# Converter_12V-0V9.net
KiCad netlist of a schematic drawn in Altium Designer
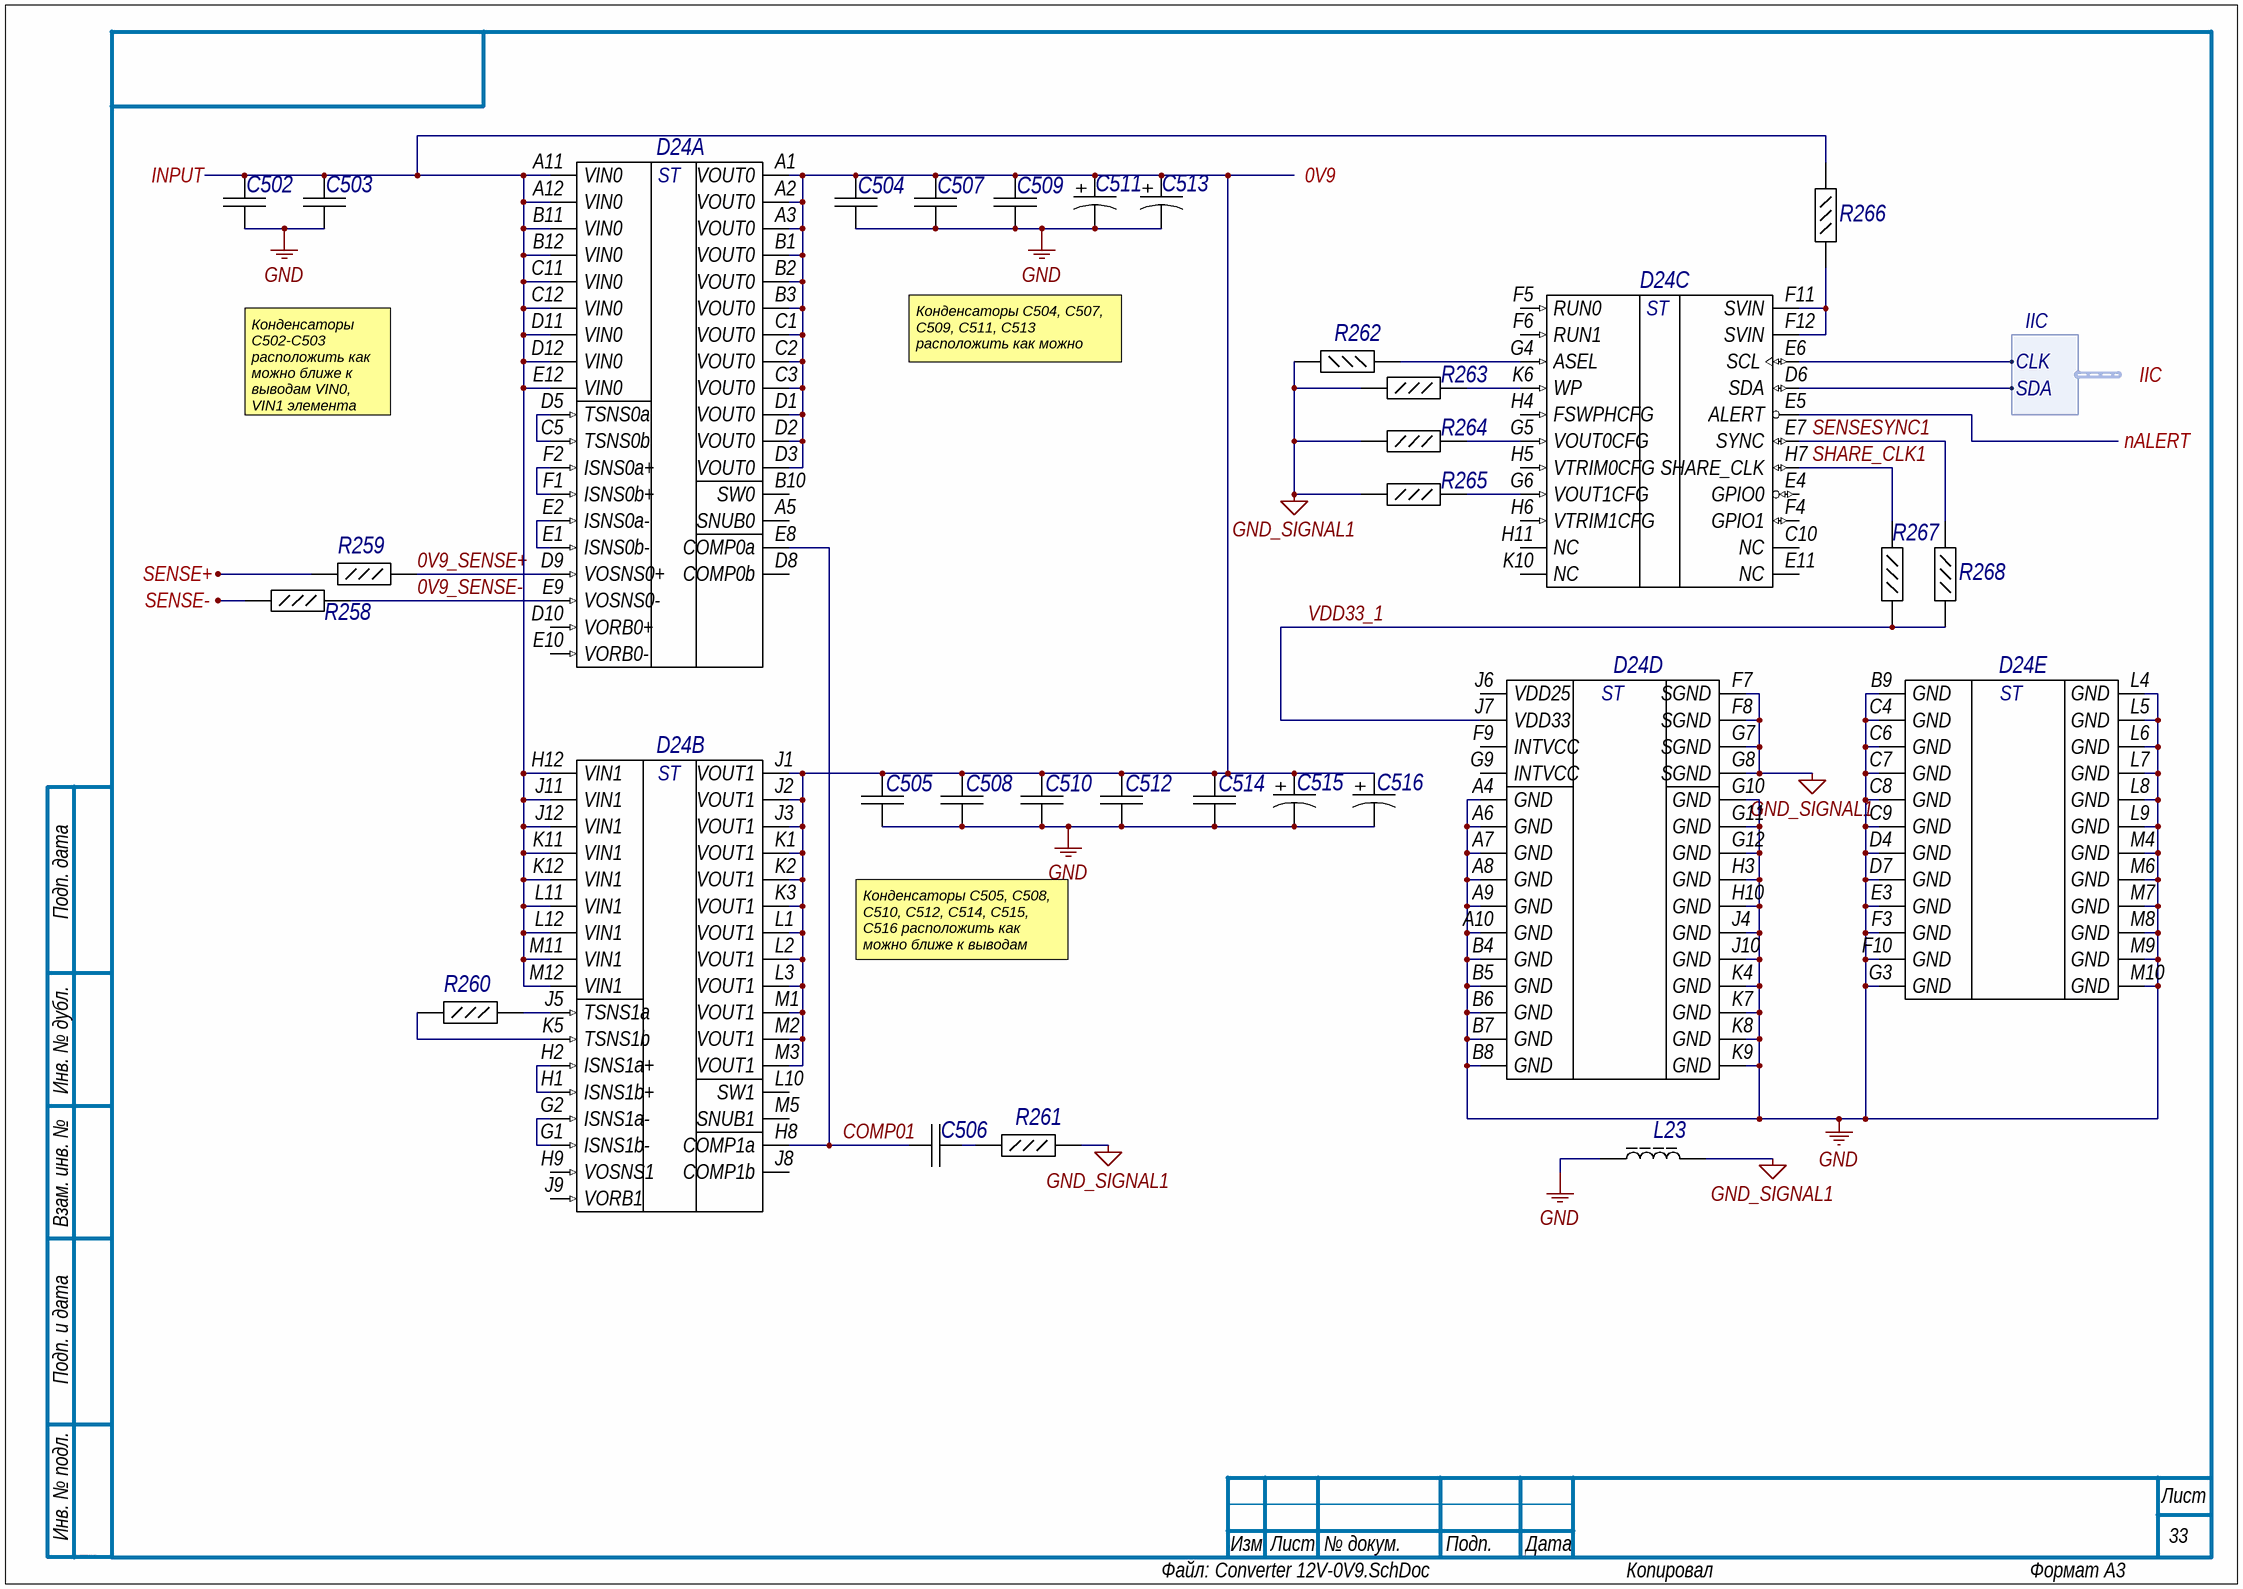
[diagram p0: Converter 12V-0V9.SchDoc]

(export (version "E")
  (design (tool "Eeschema 10.0.6"))
  (components
    (comp (ref "C502")
      (value "GRM31CR61E226KE15L")
      (footprint "CAPC3216X180X55ML20T25")
      (description "Chip Capacitor, 22 uF, +/- 10%, 25 V, -55 to 85 degC, 1206 (3216 Metric), RoHS, Tape and Reel")
      (fields (field (name "TOLERANCE") "10%"))
      (libsource (lib "MiniPC DB") (part "CAP_NP"))
    )
    (comp (ref "C503")
      (value "GRM31CR61E226KE15L")
      (footprint "CAPC3216X180X55ML20T25")
      (description "Chip Capacitor, 22 uF, +/- 10%, 25 V, -55 to 85 degC, 1206 (3216 Metric), RoHS, Tape and Reel")
      (fields (field (name "TOLERANCE") "10%"))
      (libsource (lib "MiniPC DB") (part "CAP_NP"))
    )
    (comp (ref "C504")
      (value "GRM31CR60J107ME39L")
      (footprint "CAPC3216X190X55ML30T25")
      (description "Chip Capacitor, 100 uF, +/- 20%, 6.3 V, -55 to 85 degC, 1206 (3216 Metric), RoHS, Tape and Reel")
      (fields (field (name "TOLERANCE") "20%"))
      (libsource (lib "MiniPC DB") (part "CAP_NP"))
    )
    (comp (ref "C505")
      (value "GRM31CR60J107ME39L")
      (footprint "CAPC3216X190X55ML30T25")
      (description "Chip Capacitor, 100 uF, +/- 20%, 6.3 V, -55 to 85 degC, 1206 (3216 Metric), RoHS, Tape and Reel")
      (fields (field (name "TOLERANCE") "20%"))
      (libsource (lib "MiniPC DB") (part "CAP_NP"))
    )
    (comp (ref "C506")
      (value "VJ0402Y182JXJCW1BC")
      (footprint "CAPC1005X55X23NL05T8")
      (description "Chip Capacitor, 1.8 nF, +/- 5%, 16 V, -55 to 125 degC, 0402 (1005 Metric), RoHS, Tape and Reel")
      (fields (field (name "TOLERANCE") "5%"))
      (libsource (lib "MiniPC DB") (part "CAP_NP"))
    )
    (comp (ref "C507")
      (value "GRM31CR60J107ME39L")
      (footprint "CAPC3216X190X55ML30T25")
      (description "Chip Capacitor, 100 uF, +/- 20%, 6.3 V, -55 to 85 degC, 1206 (3216 Metric), RoHS, Tape and Reel")
      (fields (field (name "TOLERANCE") "20%"))
      (libsource (lib "MiniPC DB") (part "CAP_NP"))
    )
    (comp (ref "C508")
      (value "GRM31CR60J107ME39L")
      (footprint "CAPC3216X190X55ML30T25")
      (description "Chip Capacitor, 100 uF, +/- 20%, 6.3 V, -55 to 85 degC, 1206 (3216 Metric), RoHS, Tape and Reel")
      (fields (field (name "TOLERANCE") "20%"))
      (libsource (lib "MiniPC DB") (part "CAP_NP"))
    )
    (comp (ref "C509")
      (value "GRM31CR60J107ME39L")
      (footprint "CAPC3216X190X55ML30T25")
      (description "Chip Capacitor, 100 uF, +/- 20%, 6.3 V, -55 to 85 degC, 1206 (3216 Metric), RoHS, Tape and Reel")
      (fields (field (name "TOLERANCE") "20%"))
      (libsource (lib "MiniPC DB") (part "CAP_NP"))
    )
    (comp (ref "C510")
      (value "GRM31CR60J107ME39L")
      (footprint "CAPC3216X190X55ML30T25")
      (description "Chip Capacitor, 100 uF, +/- 20%, 6.3 V, -55 to 85 degC, 1206 (3216 Metric), RoHS, Tape and Reel")
      (fields (field (name "TOLERANCE") "20%"))
      (libsource (lib "MiniPC DB") (part "CAP_NP"))
    )
    (comp (ref "C511")
      (value "6TPF330M9L")
      (footprint "PNSC-TPF-D3L_V")
      (description "Tantalum Capacitor, 330 uF, +/- 20%, 6.3 V, -55 to 105 degC, 2-Pin Molded, RoHS, Tape and Reel")
      (libsource (lib "MiniPC DB") (part "CAP_P"))
    )
    (comp (ref "C512")
      (value "GRM31CR60J107ME39L")
      (footprint "CAPC3216X190X55ML30T25")
      (description "Chip Capacitor, 100 uF, +/- 20%, 6.3 V, -55 to 85 degC, 1206 (3216 Metric), RoHS, Tape and Reel")
      (fields (field (name "TOLERANCE") "20%"))
      (libsource (lib "MiniPC DB") (part "CAP_NP"))
    )
    (comp (ref "C513")
      (value "6TPF330M9L")
      (footprint "PNSC-TPF-D3L_V")
      (description "Tantalum Capacitor, 330 uF, +/- 20%, 6.3 V, -55 to 105 degC, 2-Pin Molded, RoHS, Tape and Reel")
      (libsource (lib "MiniPC DB") (part "CAP_P"))
    )
    (comp (ref "C514")
      (value "GRM31CR60J107ME39L")
      (footprint "CAPC3216X190X55ML30T25")
      (description "Chip Capacitor, 100 uF, +/- 20%, 6.3 V, -55 to 85 degC, 1206 (3216 Metric), RoHS, Tape and Reel")
      (fields (field (name "TOLERANCE") "20%"))
      (libsource (lib "MiniPC DB") (part "CAP_NP"))
    )
    (comp (ref "C515")
      (value "6TPF330M9L")
      (footprint "PNSC-TPF-D3L_V")
      (description "Tantalum Capacitor, 330 uF, +/- 20%, 6.3 V, -55 to 105 degC, 2-Pin Molded, RoHS, Tape and Reel")
      (libsource (lib "MiniPC DB") (part "CAP_P"))
    )
    (comp (ref "C516")
      (value "6TPF330M9L")
      (footprint "PNSC-TPF-D3L_V")
      (description "Tantalum Capacitor, 330 uF, +/- 20%, 6.3 V, -55 to 105 degC, 2-Pin Molded, RoHS, Tape and Reel")
      (libsource (lib "MiniPC DB") (part "CAP_P"))
    )
    (comp (ref "D24")
      (value "LTM4677IY#PBF")
      (footprint "LT-BGA-144-05-08-1920_V")
      (fields (field (name "MANUFACTURER") "Linear Technology"))
      (libsource (lib "MiniPC DB") (part "LTM4677I"))
    )
    (comp (ref "L23")
      (value "742792609")
      (footprint "SMD-0603")
      (description "SMD EMI Suppression Ferrite Bead WE-CBF, Z = 30 Ohm")
      (libsource (lib "MiniPC DB") (part "Choke"))
    )
    (comp (ref "R258")
      (value "ERJ-2GE0R00X")
      (footprint "RESC1005X40X25LL05T05")
      (description "Chip Resistor, 0 mOhm, +/- 5%, 100 mW, -55 to 155 degC, 0402 (1005 Metric), RoHS, Tape and Reel")
      (fields (field (name "TOLERANCE") "5%") (field (name "MANUFACTURER") "Basic Passives"))
      (libsource (lib "MiniPC DB") (part "RES-0.05"))
    )
    (comp (ref "R259")
      (value "ERJ-2GE0R00X")
      (footprint "RESC1005X40X25LL05T05")
      (description "Chip Resistor, 0 mOhm, +/- 5%, 100 mW, -55 to 155 degC, 0402 (1005 Metric), RoHS, Tape and Reel")
      (fields (field (name "TOLERANCE") "5%") (field (name "MANUFACTURER") "Basic Passives"))
      (libsource (lib "MiniPC DB") (part "RES-0.05"))
    )
    (comp (ref "R260")
      (value "ERJ-2GE0R00X")
      (footprint "RESC1005X40X25LL05T05")
      (description "Chip Resistor, 0 mOhm, +/- 5%, 100 mW, -55 to 155 degC, 0402 (1005 Metric), RoHS, Tape and Reel")
      (fields (field (name "TOLERANCE") "5%") (field (name "MANUFACTURER") "Basic Passives"))
      (libsource (lib "MiniPC DB") (part "RES-0.05"))
    )
    (comp (ref "R261")
      (value "ERJ-2RKF1782X")
      (footprint "RESC1005X40X25LL05T05")
      (description "Chip Resistor, 17.8 KOhm, +/- 1%, 100 mW, -55 to 155 degC, 0402 (1005 Metric), RoHS, Tape and Reel")
      (fields (field (name "TOLERANCE") "1%") (field (name "MANUFACTURER") "Basic Passives"))
      (libsource (lib "MiniPC DB") (part "RES-0.05"))
    )
    (comp (ref "R262")
      (value "ERJ-2RKF1651X")
      (footprint "RESC1005X40X25LL05T05")
      (description "Chip Resistor, 1.65 KOhm, +/- 1%, 100 mW, -55 to 155 degC, 0402 (1005 Metric), RoHS, Tape and Reel")
      (fields (field (name "TOLERANCE") "1%") (field (name "MANUFACTURER") "Basic Passives"))
      (libsource (lib "") (part "RES-0.05_2"))
    )
    (comp (ref "R263")
      (value "ERJ-2RKF1002X")
      (footprint "RESC1005X40X25LL05T05")
      (description "Chip Resistor, 10 KOhm, +/- 1%, 100 mW, -55 to 155 degC, 0402 (1005 Metric), RoHS, Tape and Reel")
      (fields (field (name "TOLERANCE") "1%") (field (name "MANUFACTURER") "Basic Passives"))
      (libsource (lib "MiniPC DB") (part "RES-0.05"))
    )
    (comp (ref "R264")
      (value "ERJ-2RKF1651X")
      (footprint "RESC1005X40X25LL05T05")
      (description "Chip Resistor, 1.65 KOhm, +/- 1%, 100 mW, -55 to 155 degC, 0402 (1005 Metric), RoHS, Tape and Reel")
      (fields (field (name "TOLERANCE") "1%") (field (name "MANUFACTURER") "Basic Passives"))
      (libsource (lib "MiniPC DB") (part "RES-0.05"))
    )
    (comp (ref "R265")
      (value "ERJ-2RKF1651X")
      (footprint "RESC1005X40X25LL05T05")
      (description "Chip Resistor, 1.65 KOhm, +/- 1%, 100 mW, -55 to 155 degC, 0402 (1005 Metric), RoHS, Tape and Reel")
      (fields (field (name "TOLERANCE") "1%") (field (name "MANUFACTURER") "Basic Passives"))
      (libsource (lib "MiniPC DB") (part "RES-0.05"))
    )
    (comp (ref "R266")
      (value "ERJ-2GE0R00X")
      (footprint "RESC1005X40X25LL05T05")
      (description "Chip Resistor, 0 mOhm, +/- 5%, 100 mW, -55 to 155 degC, 0402 (1005 Metric), RoHS, Tape and Reel")
      (fields (field (name "TOLERANCE") "5%") (field (name "MANUFACTURER") "Basic Passives"))
      (libsource (lib "") (part "RES-0.05_1"))
    )
    (comp (ref "R267")
      (value "ERJ-2RKF1002X")
      (footprint "RESC1005X40X25LL05T05")
      (description "Chip Resistor, 10 KOhm, +/- 1%, 100 mW, -55 to 155 degC, 0402 (1005 Metric), RoHS, Tape and Reel")
      (fields (field (name "TOLERANCE") "1%") (field (name "MANUFACTURER") "Basic Passives"))
      (libsource (lib "") (part "RES-0.05_3"))
    )
    (comp (ref "R268")
      (value "ERJ-2RKF1002X")
      (footprint "RESC1005X40X25LL05T05")
      (description "Chip Resistor, 10 KOhm, +/- 1%, 100 mW, -55 to 155 degC, 0402 (1005 Metric), RoHS, Tape and Reel")
      (fields (field (name "TOLERANCE") "1%") (field (name "MANUFACTURER") "Basic Passives"))
      (libsource (lib "") (part "RES-0.05_3"))
    )
  )
  (nets
    (net (code "2") (name "/0V9") (class "Default")
      (node (ref "C504") (pin "2") (pinfunction "2_2") (pintype "passive"))
      (node (ref "C505") (pin "2") (pinfunction "2_2") (pintype "passive"))
      (node (ref "C507") (pin "2") (pinfunction "2_2") (pintype "passive"))
      (node (ref "C508") (pin "2") (pinfunction "2_2") (pintype "passive"))
      (node (ref "C509") (pin "2") (pinfunction "2_2") (pintype "passive"))
      (node (ref "C510") (pin "2") (pinfunction "2_2") (pintype "passive"))
      (node (ref "C511") (pin "1") (pinfunction "1_1") (pintype "passive"))
      (node (ref "C512") (pin "2") (pinfunction "2_2") (pintype "passive"))
      (node (ref "C513") (pin "1") (pinfunction "1_1") (pintype "passive"))
      (node (ref "C514") (pin "2") (pinfunction "2_2") (pintype "passive"))
      (node (ref "C515") (pin "1") (pinfunction "1_1") (pintype "passive"))
      (node (ref "C516") (pin "1") (pinfunction "1_1") (pintype "passive"))
      (node (ref "D24") (pin "A1") (pinfunction "VOUT0_A1") (pintype "power_in"))
      (node (ref "D24") (pin "A2") (pinfunction "VOUT0_A2") (pintype "power_in"))
      (node (ref "D24") (pin "A3") (pinfunction "VOUT0_A3") (pintype "power_in"))
      (node (ref "D24") (pin "B1") (pinfunction "VOUT0_B1") (pintype "power_in"))
      (node (ref "D24") (pin "B2") (pinfunction "VOUT0_B2") (pintype "power_in"))
      (node (ref "D24") (pin "B3") (pinfunction "VOUT0_B3") (pintype "power_in"))
      (node (ref "D24") (pin "C1") (pinfunction "VOUT0_C1") (pintype "power_in"))
      (node (ref "D24") (pin "C2") (pinfunction "VOUT0_C2") (pintype "power_in"))
      (node (ref "D24") (pin "C3") (pinfunction "VOUT0_C3") (pintype "power_in"))
      (node (ref "D24") (pin "D1") (pinfunction "VOUT0_D1") (pintype "power_in"))
      (node (ref "D24") (pin "D2") (pinfunction "VOUT0_D2") (pintype "power_in"))
      (node (ref "D24") (pin "D3") (pinfunction "VOUT0_D3") (pintype "power_in"))
      (node (ref "D24") (pin "J1") (pinfunction "VOUT1_J1") (pintype "power_in"))
      (node (ref "D24") (pin "J2") (pinfunction "VOUT1_J2") (pintype "power_in"))
      (node (ref "D24") (pin "J3") (pinfunction "VOUT1_J3") (pintype "power_in"))
      (node (ref "D24") (pin "K1") (pinfunction "VOUT1_K1") (pintype "power_in"))
      (node (ref "D24") (pin "K2") (pinfunction "VOUT1_K2") (pintype "power_in"))
      (node (ref "D24") (pin "K3") (pinfunction "VOUT1_K3") (pintype "power_in"))
      (node (ref "D24") (pin "L1") (pinfunction "VOUT1_L1") (pintype "power_in"))
      (node (ref "D24") (pin "L2") (pinfunction "VOUT1_L2") (pintype "power_in"))
      (node (ref "D24") (pin "L3") (pinfunction "VOUT1_L3") (pintype "power_in"))
      (node (ref "D24") (pin "M1") (pinfunction "VOUT1_M1") (pintype "power_in"))
      (node (ref "D24") (pin "M2") (pinfunction "VOUT1_M2") (pintype "power_in"))
      (node (ref "D24") (pin "M3") (pinfunction "VOUT1_M3") (pintype "power_in"))
    )
    (net (code "3") (name "/0V9_SENSE+") (class "Default")
      (node (ref "D24") (pin "D9") (pinfunction "VOSNS0+_D9") (pintype "input"))
      (node (ref "R259") (pin "1") (pinfunction "1_1") (pintype "passive"))
    )
    (net (code "4") (name "/0V9_SENSE-") (class "Default")
      (node (ref "D24") (pin "E9") (pinfunction "VOSNS0-_E9") (pintype "input"))
      (node (ref "R258") (pin "1") (pinfunction "1_1") (pintype "passive"))
    )
    (net (code "5") (name "/CLK") (class "Default")
      (node (ref "D24") (pin "E6") (pinfunction "SCL_E6") (pintype "bidirectional"))
    )
    (net (code "6") (name "/COMP01") (class "Default")
      (node (ref "C506") (pin "2") (pinfunction "2_2") (pintype "passive"))
      (node (ref "D24") (pin "E8") (pinfunction "COMP0a_E8") (pintype "passive"))
      (node (ref "D24") (pin "H8") (pinfunction "COMP1a_H8") (pintype "passive"))
    )
    (net (code "7") (name "/INPUT") (class "Default")
      (node (ref "C502") (pin "2") (pinfunction "2_2") (pintype "passive"))
      (node (ref "C503") (pin "2") (pinfunction "2_2") (pintype "passive"))
      (node (ref "D24") (pin "A11") (pinfunction "VIN0_A11") (pintype "power_in"))
      (node (ref "D24") (pin "A12") (pinfunction "VIN0_A12") (pintype "power_in"))
      (node (ref "D24") (pin "B11") (pinfunction "VIN0_B11") (pintype "power_in"))
      (node (ref "D24") (pin "B12") (pinfunction "VIN0_B12") (pintype "power_in"))
      (node (ref "D24") (pin "C11") (pinfunction "VIN0_C11") (pintype "power_in"))
      (node (ref "D24") (pin "C12") (pinfunction "VIN0_C12") (pintype "power_in"))
      (node (ref "D24") (pin "D11") (pinfunction "VIN0_D11") (pintype "power_in"))
      (node (ref "D24") (pin "D12") (pinfunction "VIN0_D12") (pintype "power_in"))
      (node (ref "D24") (pin "E12") (pinfunction "VIN0_E12") (pintype "power_in"))
      (node (ref "D24") (pin "H12") (pinfunction "VIN1_H12") (pintype "power_in"))
      (node (ref "D24") (pin "J11") (pinfunction "VIN1_J11") (pintype "power_in"))
      (node (ref "D24") (pin "J12") (pinfunction "VIN1_J12") (pintype "power_in"))
      (node (ref "D24") (pin "K11") (pinfunction "VIN1_K11") (pintype "power_in"))
      (node (ref "D24") (pin "K12") (pinfunction "VIN1_K12") (pintype "power_in"))
      (node (ref "D24") (pin "L11") (pinfunction "VIN1_L11") (pintype "power_in"))
      (node (ref "D24") (pin "L12") (pinfunction "VIN1_L12") (pintype "power_in"))
      (node (ref "D24") (pin "M11") (pinfunction "VIN1_M11") (pintype "power_in"))
      (node (ref "D24") (pin "M12") (pinfunction "VIN1_M12") (pintype "power_in"))
      (node (ref "R266") (pin "2") (pinfunction "2_2") (pintype "passive"))
    )
    (net (code "8") (name "/SDA") (class "Default")
      (node (ref "D24") (pin "D6") (pinfunction "SDA_D6") (pintype "bidirectional"))
    )
    (net (code "9") (name "/SENSE+") (class "Default")
      (node (ref "R259") (pin "2") (pinfunction "2_2") (pintype "passive"))
    )
    (net (code "10") (name "/SENSE-") (class "Default")
      (node (ref "R258") (pin "2") (pinfunction "2_2") (pintype "passive"))
    )
    (net (code "11") (name "/SENSESYNC1") (class "Default")
      (node (ref "D24") (pin "E7") (pinfunction "SYNC_E7") (pintype "bidirectional"))
      (node (ref "R268") (pin "1") (pinfunction "1_1") (pintype "passive"))
    )
    (net (code "12") (name "/SHARE_CLK1") (class "Default")
      (node (ref "D24") (pin "H7") (pinfunction "SHARE_CLK_H7") (pintype "bidirectional"))
      (node (ref "R267") (pin "1") (pinfunction "1_1") (pintype "passive"))
    )
    (net (code "13") (name "/VDD33_1") (class "Default")
      (node (ref "D24") (pin "J7") (pinfunction "VDD33_J7") (pintype "power_in"))
      (node (ref "R267") (pin "2") (pinfunction "2_2") (pintype "passive"))
      (node (ref "R268") (pin "2") (pinfunction "2_2") (pintype "passive"))
    )
    (net (code "14") (name "/nALERT") (class "Default")
      (node (ref "D24") (pin "E5") (pinfunction "ALERT_E5") (pintype "open_collector"))
    )
    (net (code "16") (name "GND") (class "Default")
      (node (ref "C502") (pin "1") (pinfunction "1_1") (pintype "passive"))
      (node (ref "C503") (pin "1") (pinfunction "1_1") (pintype "passive"))
      (node (ref "C504") (pin "1") (pinfunction "1_1") (pintype "passive"))
      (node (ref "C505") (pin "1") (pinfunction "1_1") (pintype "passive"))
      (node (ref "C507") (pin "1") (pinfunction "1_1") (pintype "passive"))
      (node (ref "C508") (pin "1") (pinfunction "1_1") (pintype "passive"))
      (node (ref "C509") (pin "1") (pinfunction "1_1") (pintype "passive"))
      (node (ref "C510") (pin "1") (pinfunction "1_1") (pintype "passive"))
      (node (ref "C511") (pin "2") (pinfunction "2_2") (pintype "passive"))
      (node (ref "C512") (pin "1") (pinfunction "1_1") (pintype "passive"))
      (node (ref "C513") (pin "2") (pinfunction "2_2") (pintype "passive"))
      (node (ref "C514") (pin "1") (pinfunction "1_1") (pintype "passive"))
      (node (ref "C515") (pin "2") (pinfunction "2_2") (pintype "passive"))
      (node (ref "C516") (pin "2") (pinfunction "2_2") (pintype "passive"))
      (node (ref "D24") (pin "A10") (pinfunction "GND_A10") (pintype "passive"))
      (node (ref "D24") (pin "A4") (pinfunction "GND_A4") (pintype "passive"))
      (node (ref "D24") (pin "A6") (pinfunction "GND_A6") (pintype "passive"))
      (node (ref "D24") (pin "A7") (pinfunction "GND_A7") (pintype "passive"))
      (node (ref "D24") (pin "A8") (pinfunction "GND_A8") (pintype "passive"))
      (node (ref "D24") (pin "A9") (pinfunction "GND_A9") (pintype "passive"))
      (node (ref "D24") (pin "B4") (pinfunction "GND_B4") (pintype "passive"))
      (node (ref "D24") (pin "B5") (pinfunction "GND_B5") (pintype "passive"))
      (node (ref "D24") (pin "B6") (pinfunction "GND_B6") (pintype "passive"))
      (node (ref "D24") (pin "B7") (pinfunction "GND_B7") (pintype "passive"))
      (node (ref "D24") (pin "B8") (pinfunction "GND_B8") (pintype "passive"))
      (node (ref "D24") (pin "B9") (pinfunction "GND_B9") (pintype "passive"))
      (node (ref "D24") (pin "C4") (pinfunction "GND_C4") (pintype "passive"))
      (node (ref "D24") (pin "C6") (pinfunction "GND_C6") (pintype "passive"))
      (node (ref "D24") (pin "C7") (pinfunction "GND_C7") (pintype "passive"))
      (node (ref "D24") (pin "C8") (pinfunction "GND_C8") (pintype "passive"))
      (node (ref "D24") (pin "C9") (pinfunction "GND_C9") (pintype "passive"))
      (node (ref "D24") (pin "D4") (pinfunction "GND_D4") (pintype "passive"))
      (node (ref "D24") (pin "D7") (pinfunction "GND_D7") (pintype "passive"))
      (node (ref "D24") (pin "E3") (pinfunction "GND_E3") (pintype "passive"))
      (node (ref "D24") (pin "F10") (pinfunction "GND_F10") (pintype "passive"))
      (node (ref "D24") (pin "F3") (pinfunction "GND_F3") (pintype "passive"))
      (node (ref "D24") (pin "G10") (pinfunction "GND_G10") (pintype "passive"))
      (node (ref "D24") (pin "G11") (pinfunction "GND_G11") (pintype "passive"))
      (node (ref "D24") (pin "G12") (pinfunction "GND_G12") (pintype "passive"))
      (node (ref "D24") (pin "G3") (pinfunction "GND_G3") (pintype "passive"))
      (node (ref "D24") (pin "H10") (pinfunction "GND_H10") (pintype "passive"))
      (node (ref "D24") (pin "H3") (pinfunction "GND_H3") (pintype "passive"))
      (node (ref "D24") (pin "J10") (pinfunction "GND_J10") (pintype "passive"))
      (node (ref "D24") (pin "J4") (pinfunction "GND_J4") (pintype "passive"))
      (node (ref "D24") (pin "K4") (pinfunction "GND_K4") (pintype "passive"))
      (node (ref "D24") (pin "K7") (pinfunction "GND_K7") (pintype "passive"))
      (node (ref "D24") (pin "K8") (pinfunction "GND_K8") (pintype "passive"))
      (node (ref "D24") (pin "K9") (pinfunction "GND_K9") (pintype "passive"))
      (node (ref "D24") (pin "L4") (pinfunction "GND_L4") (pintype "passive"))
      (node (ref "D24") (pin "L5") (pinfunction "GND_L5") (pintype "passive"))
      (node (ref "D24") (pin "L6") (pinfunction "GND_L6") (pintype "passive"))
      (node (ref "D24") (pin "L7") (pinfunction "GND_L7") (pintype "passive"))
      (node (ref "D24") (pin "L8") (pinfunction "GND_L8") (pintype "passive"))
      (node (ref "D24") (pin "L9") (pinfunction "GND_L9") (pintype "passive"))
      (node (ref "D24") (pin "M10") (pinfunction "GND_M10") (pintype "passive"))
      (node (ref "D24") (pin "M4") (pinfunction "GND_M4") (pintype "passive"))
      (node (ref "D24") (pin "M6") (pinfunction "GND_M6") (pintype "passive"))
      (node (ref "D24") (pin "M7") (pinfunction "GND_M7") (pintype "passive"))
      (node (ref "D24") (pin "M8") (pinfunction "GND_M8") (pintype "passive"))
      (node (ref "D24") (pin "M9") (pinfunction "GND_M9") (pintype "passive"))
      (node (ref "L23") (pin "1") (pinfunction "1_1") (pintype "passive"))
    )
    (net (code "17") (name "GND_SIGNAL1") (class "Default")
      (node (ref "D24") (pin "F7") (pinfunction "SGND_F7") (pintype "power_in"))
      (node (ref "D24") (pin "F8") (pinfunction "SGND_F8") (pintype "power_in"))
      (node (ref "D24") (pin "G7") (pinfunction "SGND_G7") (pintype "power_in"))
      (node (ref "D24") (pin "G8") (pinfunction "SGND_G8") (pintype "power_in"))
      (node (ref "L23") (pin "2") (pinfunction "2_2") (pintype "passive"))
      (node (ref "R261") (pin "1") (pinfunction "1_1") (pintype "passive"))
      (node (ref "R262") (pin "1") (pinfunction "1_1") (pintype "passive"))
      (node (ref "R263") (pin "2") (pinfunction "2_2") (pintype "passive"))
      (node (ref "R264") (pin "2") (pinfunction "2_2") (pintype "passive"))
      (node (ref "R265") (pin "2") (pinfunction "2_2") (pintype "passive"))
    )
    (net (code "18") (name "Net-(C506-Pad1)") (class "Default")
      (node (ref "C506") (pin "1") (pinfunction "1_1") (pintype "passive"))
      (node (ref "R261") (pin "2") (pinfunction "2_2") (pintype "passive"))
    )
    (net (code "19") (name "Net-(D24A-ISNS0a+)") (class "Default")
      (node (ref "D24") (pin "F1") (pinfunction "ISNS0b+_F1") (pintype "input"))
      (node (ref "D24") (pin "F2") (pinfunction "ISNS0a+_F2") (pintype "input"))
    )
    (net (code "20") (name "Net-(D24A-ISNS0a-)") (class "Default")
      (node (ref "D24") (pin "E1") (pinfunction "ISNS0b-_E1") (pintype "input"))
      (node (ref "D24") (pin "E2") (pinfunction "ISNS0a-_E2") (pintype "input"))
    )
    (net (code "21") (name "Net-(D24A-TSNS0a)") (class "Default")
      (node (ref "D24") (pin "C5") (pinfunction "TSNS0b_C5") (pintype "input"))
      (node (ref "D24") (pin "D5") (pinfunction "TSNS0a_D5") (pintype "input"))
    )
    (net (code "22") (name "Net-(D24B-ISNS1a+)") (class "Default")
      (node (ref "D24") (pin "H1") (pinfunction "ISNS1b+_H1") (pintype "input"))
      (node (ref "D24") (pin "H2") (pinfunction "ISNS1a+_H2") (pintype "input"))
    )
    (net (code "23") (name "Net-(D24B-ISNS1a-)") (class "Default")
      (node (ref "D24") (pin "G1") (pinfunction "ISNS1b-_G1") (pintype "input"))
      (node (ref "D24") (pin "G2") (pinfunction "ISNS1a-_G2") (pintype "input"))
    )
    (net (code "24") (name "Net-(D24B-TSNS1a)") (class "Default")
      (node (ref "D24") (pin "J5") (pinfunction "TSNS1a_J5") (pintype "input"))
      (node (ref "R260") (pin "1") (pinfunction "1_1") (pintype "passive"))
    )
    (net (code "25") (name "Net-(D24B-TSNS1b)") (class "Default")
      (node (ref "D24") (pin "K5") (pinfunction "TSNS1b_K5") (pintype "input"))
      (node (ref "R260") (pin "2") (pinfunction "2_2") (pintype "passive"))
    )
    (net (code "26") (name "Net-(D24C-ASEL)") (class "Default")
      (node (ref "D24") (pin "G4") (pinfunction "ASEL_G4") (pintype "input"))
      (node (ref "R262") (pin "2") (pinfunction "2_2") (pintype "passive"))
    )
    (net (code "27") (name "Net-(D24C-SVIN-PadF11)") (class "Default")
      (node (ref "D24") (pin "F11") (pinfunction "SVIN_F11") (pintype "passive"))
      (node (ref "D24") (pin "F12") (pinfunction "SVIN_F12") (pintype "passive"))
      (node (ref "R266") (pin "1") (pinfunction "1_1") (pintype "passive"))
    )
    (net (code "28") (name "Net-(D24C-VOUT0CFG)") (class "Default")
      (node (ref "D24") (pin "G5") (pinfunction "VOUT0CFG_G5") (pintype "input"))
      (node (ref "R264") (pin "1") (pinfunction "1_1") (pintype "passive"))
    )
    (net (code "29") (name "Net-(D24C-VOUT1CFG)") (class "Default")
      (node (ref "D24") (pin "G6") (pinfunction "VOUT1CFG_G6") (pintype "input"))
      (node (ref "R265") (pin "1") (pinfunction "1_1") (pintype "passive"))
    )
    (net (code "30") (name "Net-(D24C-WP)") (class "Default")
      (node (ref "D24") (pin "K6") (pinfunction "WP_K6") (pintype "input"))
      (node (ref "R263") (pin "1") (pinfunction "1_1") (pintype "passive"))
    )
    (net (code "31") (name "unconnected-(D24A-COMP0b-PadD8)") (class "Default")
      (node (ref "D24") (pin "D8") (pinfunction "COMP0b_D8") (pintype "passive"))
    )
    (net (code "32") (name "unconnected-(D24A-SNUB0-PadA5)") (class "Default")
      (node (ref "D24") (pin "A5") (pinfunction "SNUB0_A5") (pintype "passive"))
    )
    (net (code "33") (name "unconnected-(D24A-SW0-PadB10)") (class "Default")
      (node (ref "D24") (pin "B10") (pinfunction "SW0_B10") (pintype "passive"))
    )
    (net (code "34") (name "unconnected-(D24A-VORB0+-PadD10)") (class "Default")
      (node (ref "D24") (pin "D10") (pinfunction "VORB0+_D10") (pintype "input"))
    )
    (net (code "35") (name "unconnected-(D24A-VORB0--PadE10)") (class "Default")
      (node (ref "D24") (pin "E10") (pinfunction "VORB0-_E10") (pintype "input"))
    )
    (net (code "36") (name "unconnected-(D24B-COMP1b-PadJ8)") (class "Default")
      (node (ref "D24") (pin "J8") (pinfunction "COMP1b_J8") (pintype "passive"))
    )
    (net (code "37") (name "unconnected-(D24B-SNUB1-PadM5)") (class "Default")
      (node (ref "D24") (pin "M5") (pinfunction "SNUB1_M5") (pintype "passive"))
    )
    (net (code "38") (name "unconnected-(D24B-SW1-PadL10)") (class "Default")
      (node (ref "D24") (pin "L10") (pinfunction "SW1_L10") (pintype "passive"))
    )
    (net (code "39") (name "unconnected-(D24B-VORB1-PadJ9)") (class "Default")
      (node (ref "D24") (pin "J9") (pinfunction "VORB1_J9") (pintype "input"))
    )
    (net (code "40") (name "unconnected-(D24B-VOSNS1-PadH9)") (class "Default")
      (node (ref "D24") (pin "H9") (pinfunction "VOSNS1_H9") (pintype "input"))
    )
    (net (code "41") (name "unconnected-(D24C-FSWPHCFG-PadH4)") (class "Default")
      (node (ref "D24") (pin "H4") (pinfunction "FSWPHCFG_H4") (pintype "input"))
    )
    (net (code "42") (name "unconnected-(D24C-GPIO0-PadE4)") (class "Default")
      (node (ref "D24") (pin "E4") (pinfunction "GPIO0_E4") (pintype "bidirectional"))
    )
    (net (code "43") (name "unconnected-(D24C-GPIO1-PadF4)") (class "Default")
      (node (ref "D24") (pin "F4") (pinfunction "GPIO1_F4") (pintype "bidirectional"))
    )
    (net (code "44") (name "unconnected-(D24C-NC-PadC10)") (class "Default")
      (node (ref "D24") (pin "C10") (pinfunction "NC_C10") (pintype "passive"))
    )
    (net (code "45") (name "unconnected-(D24C-NC-PadE11)") (class "Default")
      (node (ref "D24") (pin "E11") (pinfunction "NC_E11") (pintype "passive"))
    )
    (net (code "46") (name "unconnected-(D24C-NC-PadH11)") (class "Default")
      (node (ref "D24") (pin "H11") (pinfunction "NC_H11") (pintype "passive"))
    )
    (net (code "47") (name "unconnected-(D24C-NC-PadK10)") (class "Default")
      (node (ref "D24") (pin "K10") (pinfunction "NC_K10") (pintype "passive"))
    )
    (net (code "48") (name "unconnected-(D24C-RUN0-PadF5)") (class "Default")
      (node (ref "D24") (pin "F5") (pinfunction "RUN0_F5") (pintype "input"))
    )
    (net (code "49") (name "unconnected-(D24C-RUN1-PadF6)") (class "Default")
      (node (ref "D24") (pin "F6") (pinfunction "RUN1_F6") (pintype "input"))
    )
    (net (code "50") (name "unconnected-(D24C-VTRIM0CFG-PadH5)") (class "Default")
      (node (ref "D24") (pin "H5") (pinfunction "VTRIM0CFG_H5") (pintype "input"))
    )
    (net (code "51") (name "unconnected-(D24C-VTRIM1CFG-PadH6)") (class "Default")
      (node (ref "D24") (pin "H6") (pinfunction "VTRIM1CFG_H6") (pintype "input"))
    )
    (net (code "52") (name "unconnected-(D24D-INTVCC-PadF9)") (class "Default")
      (node (ref "D24") (pin "F9") (pinfunction "INTVCC_F9") (pintype "power_in"))
    )
    (net (code "53") (name "unconnected-(D24D-INTVCC-PadG9)") (class "Default")
      (node (ref "D24") (pin "G9") (pinfunction "INTVCC_G9") (pintype "power_in"))
    )
    (net (code "54") (name "unconnected-(D24D-VDD25-PadJ6)") (class "Default")
      (node (ref "D24") (pin "J6") (pinfunction "VDD25_J6") (pintype "power_in"))
    )
  )
)
